# m328p_rfm69_node.net
KiCad netlist of a schematic drawn in EAGLE
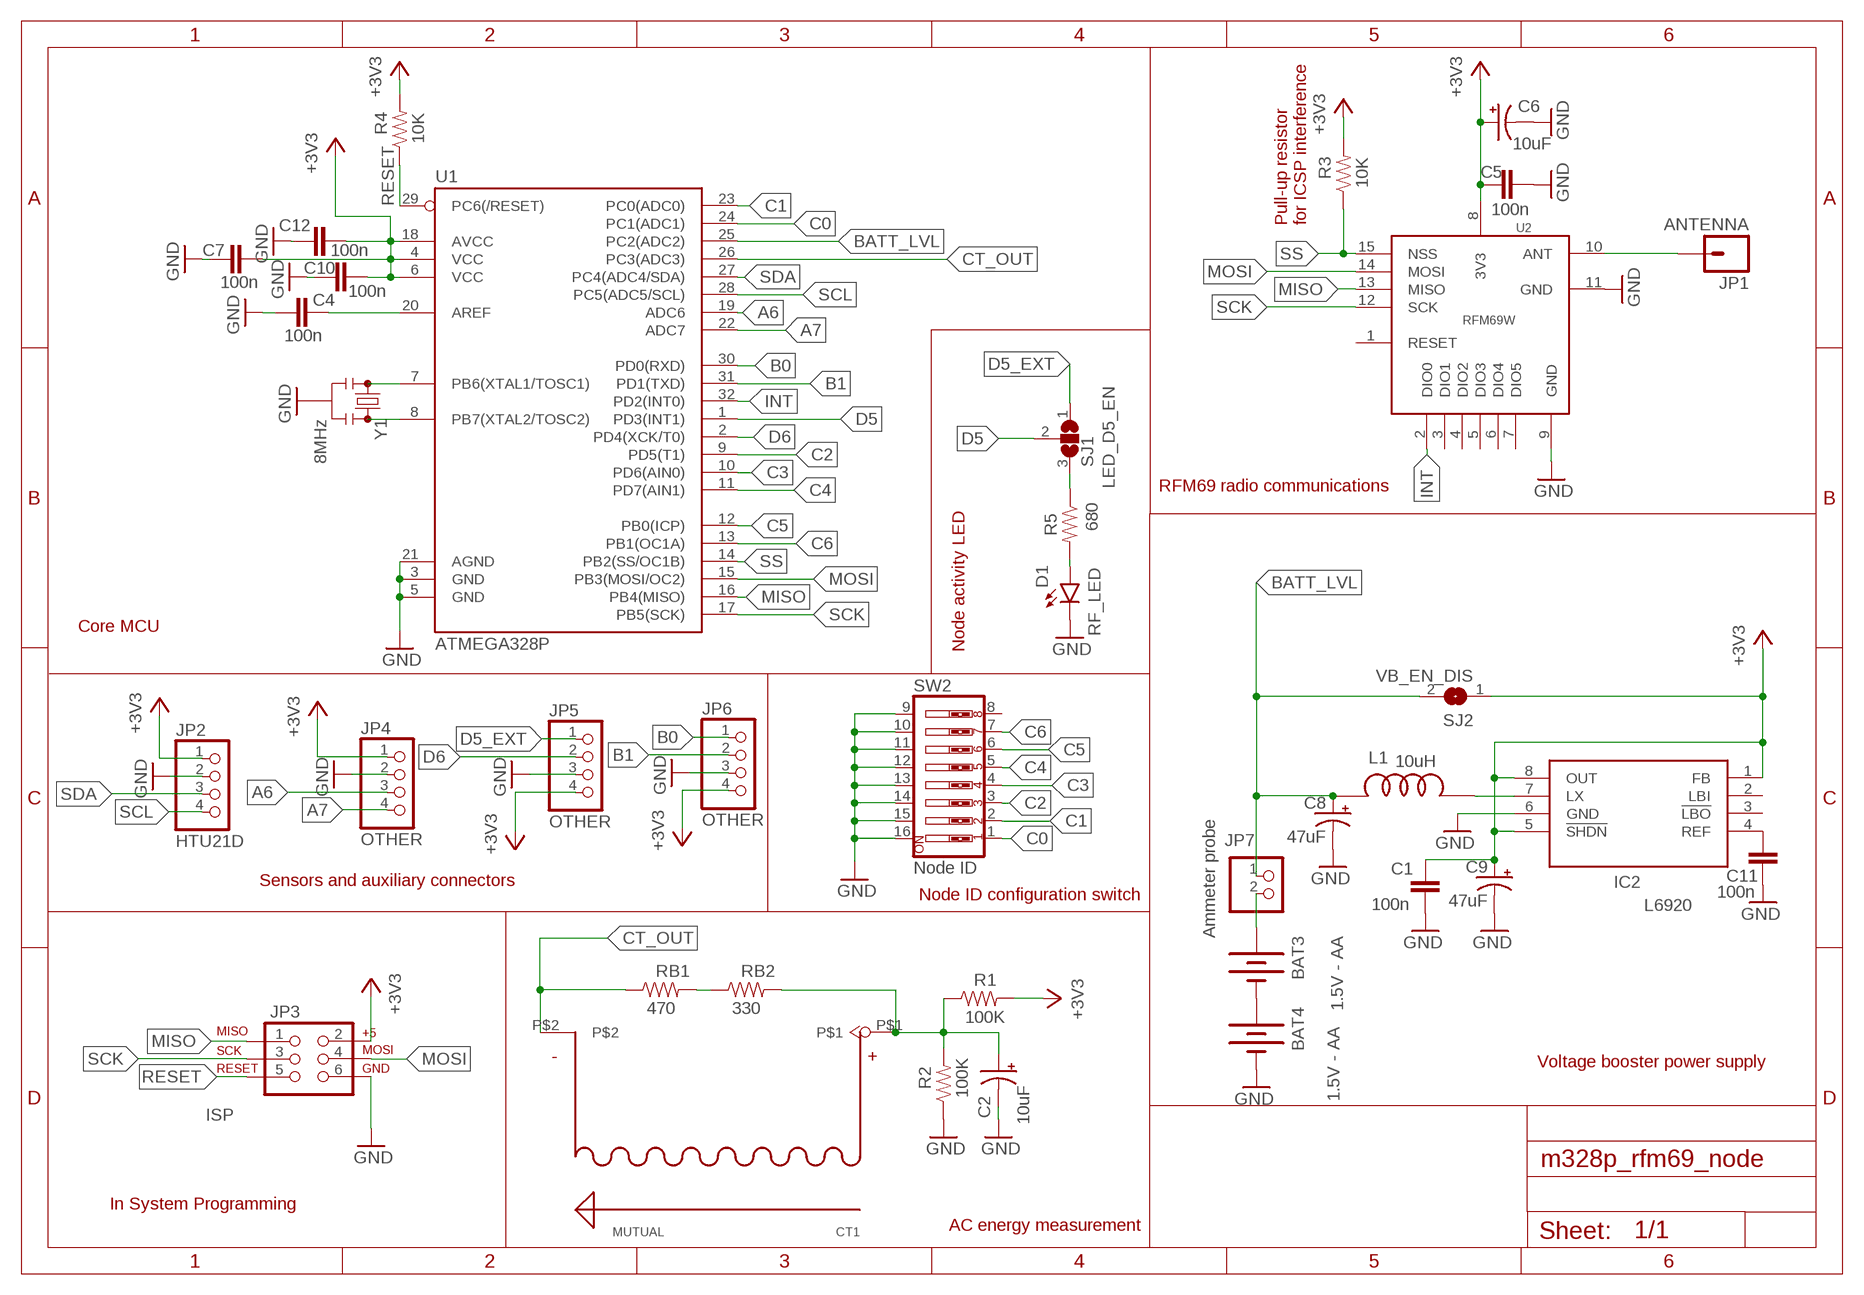
[diagram p0: schematic, sheet 1]

(export (version "E")
  (design (tool "Eeschema 10.0.6"))
  (components
    (comp (ref "BAT3")
      (value "1.5V - AA")
      (footprint "eagle-import:BATTERY-AAA-KIT")
      (libsource (lib "eagle-import") (part "BATTERYAAA-KIT"))
    )
    (comp (ref "BAT4")
      (value "1.5V - AA")
      (footprint "eagle-import:BATTERY-AAA-KIT")
      (libsource (lib "eagle-import") (part "BATTERYAAA-KIT"))
    )
    (comp (ref "C1")
      (value "100n")
      (footprint "eagle-import:0805")
      (libsource (lib "eagle-import") (part "CAP0805"))
    )
    (comp (ref "C2")
      (value "10uF")
      (footprint "eagle-import:EIA3528")
      (libsource (lib "eagle-import") (part "47UF-TANT"))
    )
    (comp (ref "C4")
      (value "100n")
      (footprint "eagle-import:0805")
      (libsource (lib "eagle-import") (part "CAP0805"))
    )
    (comp (ref "C5")
      (value "100n")
      (footprint "eagle-import:0805")
      (libsource (lib "eagle-import") (part "CAP0805"))
    )
    (comp (ref "C6")
      (value "10uF")
      (footprint "eagle-import:EIA3528")
      (libsource (lib "eagle-import") (part "47UF-TANT"))
    )
    (comp (ref "C7")
      (value "100n")
      (footprint "eagle-import:0805")
      (libsource (lib "eagle-import") (part "CAP0805"))
    )
    (comp (ref "C8")
      (value "47uF")
      (footprint "eagle-import:EIA3528")
      (libsource (lib "eagle-import") (part "47UF-TANT"))
    )
    (comp (ref "C9")
      (value "47uF")
      (footprint "eagle-import:EIA3528")
      (libsource (lib "eagle-import") (part "47UF-TANT"))
    )
    (comp (ref "C10")
      (value "100n")
      (footprint "eagle-import:0805")
      (libsource (lib "eagle-import") (part "CAP0805"))
    )
    (comp (ref "C11")
      (value "100n")
      (footprint "eagle-import:0805")
      (libsource (lib "eagle-import") (part "CAP0805"))
    )
    (comp (ref "C12")
      (value "100n")
      (footprint "eagle-import:0805")
      (libsource (lib "eagle-import") (part "CAP0805"))
    )
    (comp (ref "CT1")
      (value "MUTUAL")
      (footprint "eagle-import:MUTUAL")
      (libsource (lib "eagle-import") (part "MUTUAL"))
    )
    (comp (ref "D1")
      (value "RF_LED")
      (footprint "eagle-import:LED-0603")
      (libsource (lib "eagle-import") (part "LED0603"))
    )
    (comp (ref "IC2")
      (value "L6920")
      (footprint "eagle-import:TSSOP8")
      (libsource (lib "eagle-import") (part "L6920TSSOP8"))
    )
    (comp (ref "JP1")
      (value "ANTENNA")
      (footprint "eagle-import:LUXEON-PAD")
      (libsource (lib "eagle-import") (part "M01SMD"))
    )
    (comp (ref "JP2")
      (value "HTU21D")
      (footprint "eagle-import:1X04")
      (libsource (lib "eagle-import") (part "PINHD-1X4"))
    )
    (comp (ref "JP3")
      (value "ISP")
      (footprint "eagle-import:2X3")
      (libsource (lib "eagle-import") (part "AVR_SPI_PRG_6PTH"))
    )
    (comp (ref "JP4")
      (value "OTHER")
      (footprint "eagle-import:1X04")
      (libsource (lib "eagle-import") (part "PINHD-1X4"))
    )
    (comp (ref "JP5")
      (value "OTHER")
      (footprint "eagle-import:1X04")
      (libsource (lib "eagle-import") (part "PINHD-1X4"))
    )
    (comp (ref "JP6")
      (value "OTHER")
      (footprint "eagle-import:1X04")
      (libsource (lib "eagle-import") (part "PINHD-1X4"))
    )
    (comp (ref "JP7")
      (value "Ammeter probe")
      (footprint "eagle-import:1X02")
      (libsource (lib "eagle-import") (part "PINHD-1X2"))
    )
    (comp (ref "L1")
      (value "10uH")
      (footprint "eagle-import:DLJ-4018")
      (libsource (lib "eagle-import") (part "DLJ-4018"))
    )
    (comp (ref "R1")
      (value "100K")
      (footprint "eagle-import:0805")
      (libsource (lib "eagle-import") (part "SparkFun-Resistors_RESISTOR0805-RES"))
    )
    (comp (ref "R2")
      (value "100K")
      (footprint "eagle-import:0805")
      (libsource (lib "eagle-import") (part "SparkFun-Resistors_RESISTOR0805-RES"))
    )
    (comp (ref "R3")
      (value "10K")
      (footprint "eagle-import:0805")
      (libsource (lib "eagle-import") (part "SparkFun-Resistors_RESISTOR0805-RES"))
    )
    (comp (ref "R4")
      (value "10K")
      (footprint "eagle-import:0805")
      (libsource (lib "eagle-import") (part "SparkFun-Resistors_RESISTOR0805-RES"))
    )
    (comp (ref "R5")
      (value "680")
      (footprint "eagle-import:0805")
      (libsource (lib "eagle-import") (part "RESISTOR0805-RES"))
    )
    (comp (ref "RB1")
      (value "470")
      (footprint "eagle-import:0805")
      (libsource (lib "eagle-import") (part "SparkFun-Resistors_RESISTOR0805-RES"))
    )
    (comp (ref "RB2")
      (value "330")
      (footprint "eagle-import:0805")
      (libsource (lib "eagle-import") (part "SparkFun-Resistors_RESISTOR0805-RES"))
    )
    (comp (ref "SJ1")
      (value "LED_D5_EN")
      (footprint "eagle-import:SJ_2")
      (libsource (lib "eagle-import") (part "SJ2W"))
    )
    (comp (ref "SJ2")
      (value "VB_EN_DIS")
      (footprint "eagle-import:SJ")
      (libsource (lib "eagle-import") (part "SJ"))
    )
    (comp (ref "SW2")
      (value "Node ID")
      (footprint "eagle-import:DIPSWITCH-08-50MIL")
      (libsource (lib "eagle-import") (part "SW_DIP-8-SMT-HALFSIZE"))
    )
    (comp (ref "U1")
      (value "ATMEGA328P")
      (footprint "eagle-import:TQFP32-08")
      (libsource (lib "eagle-import") (part "ATMEGA328P_TQFP"))
    )
    (comp (ref "U2")
      (value "RFM69W")
      (footprint "eagle-import:RFM69W")
      (libsource (lib "eagle-import") (part "RFM69W"))
    )
    (comp (ref "Y1")
      (value "8MHz")
      (footprint "eagle-import:RESONATOR-SMD_MED")
      (libsource (lib "eagle-import") (part "RESONATOR4MHZ"))
    )
  )
  (nets
    (net (code "1") (name "+3V3") (class "Default")
      (node (ref "C1") (pin "1") (pinfunction "1_1") (pintype "passive"))
      (node (ref "C10") (pin "2") (pinfunction "2_2") (pintype "passive"))
      (node (ref "C12") (pin "2") (pinfunction "2_2") (pintype "passive"))
      (node (ref "C5") (pin "1") (pinfunction "1_1") (pintype "passive"))
      (node (ref "C6") (pin "A") (pinfunction "+_A") (pintype "passive"))
      (node (ref "C7") (pin "2") (pinfunction "2_2") (pintype "passive"))
      (node (ref "C9") (pin "A") (pinfunction "+_A") (pintype "passive"))
      (node (ref "IC2") (pin "1") (pinfunction "FB_1") (pintype "bidirectional"))
      (node (ref "IC2") (pin "5") (pinfunction "~{SHDN}_5") (pintype "bidirectional"))
      (node (ref "IC2") (pin "8") (pinfunction "OUT_8") (pintype "bidirectional"))
      (node (ref "JP2") (pin "1") (pinfunction "1_1") (pintype "passive"))
      (node (ref "JP3") (pin "2") (pinfunction "2_2") (pintype "passive"))
      (node (ref "JP4") (pin "1") (pinfunction "1_1") (pintype "passive"))
      (node (ref "JP5") (pin "4") (pinfunction "4_4") (pintype "passive"))
      (node (ref "JP6") (pin "4") (pinfunction "4_4") (pintype "passive"))
      (node (ref "R1") (pin "2") (pinfunction "2_2") (pintype "passive"))
      (node (ref "R3") (pin "2") (pinfunction "2_2") (pintype "passive"))
      (node (ref "R4") (pin "2") (pinfunction "2_2") (pintype "passive"))
      (node (ref "SJ2") (pin "1") (pinfunction "1_1") (pintype "passive"))
      (node (ref "U1") (pin "18") (pinfunction "AVCC_18") (pintype "bidirectional"))
      (node (ref "U1") (pin "4") (pinfunction "VCC_4") (pintype "bidirectional"))
      (node (ref "U1") (pin "6") (pinfunction "VCC_6") (pintype "bidirectional"))
      (node (ref "U2") (pin "8") (pinfunction "3V3_8") (pintype "bidirectional"))
    )
    (net (code "2") (name "A6") (class "Default")
      (node (ref "JP4") (pin "3") (pinfunction "3_3") (pintype "passive"))
      (node (ref "U1") (pin "19") (pinfunction "ADC6_19") (pintype "bidirectional"))
    )
    (net (code "3") (name "A7") (class "Default")
      (node (ref "JP4") (pin "4") (pinfunction "4_4") (pintype "passive"))
      (node (ref "U1") (pin "22") (pinfunction "ADC7_22") (pintype "bidirectional"))
    )
    (net (code "4") (name "B0") (class "Default")
      (node (ref "JP6") (pin "1") (pinfunction "1_1") (pintype "passive"))
      (node (ref "U1") (pin "30") (pinfunction "PD0(RXD)_30") (pintype "bidirectional"))
    )
    (net (code "5") (name "B1") (class "Default")
      (node (ref "JP6") (pin "2") (pinfunction "2_2") (pintype "passive"))
      (node (ref "U1") (pin "31") (pinfunction "PD1(TXD)_31") (pintype "bidirectional"))
    )
    (net (code "6") (name "BATT_LVL") (class "Default")
      (node (ref "C8") (pin "A") (pinfunction "+_A") (pintype "passive"))
      (node (ref "JP7") (pin "1") (pinfunction "1_1") (pintype "passive"))
      (node (ref "L1") (pin "P$2") (pinfunction "2_P$2") (pintype "bidirectional"))
      (node (ref "SJ2") (pin "2") (pinfunction "2_2") (pintype "passive"))
      (node (ref "U1") (pin "25") (pinfunction "PC2(ADC2)_25") (pintype "bidirectional"))
    )
    (net (code "7") (name "C0") (class "Default")
      (node (ref "SW2") (pin "1") (pinfunction "1_1") (pintype "passive"))
      (node (ref "U1") (pin "24") (pinfunction "PC1(ADC1)_24") (pintype "bidirectional"))
    )
    (net (code "8") (name "C1") (class "Default")
      (node (ref "SW2") (pin "2") (pinfunction "2_2") (pintype "passive"))
      (node (ref "U1") (pin "23") (pinfunction "PC0(ADC0)_23") (pintype "bidirectional"))
    )
    (net (code "9") (name "C2") (class "Default")
      (node (ref "SW2") (pin "3") (pinfunction "3_3") (pintype "passive"))
      (node (ref "U1") (pin "9") (pinfunction "PD5(T1)_9") (pintype "bidirectional"))
    )
    (net (code "10") (name "C3") (class "Default")
      (node (ref "SW2") (pin "4") (pinfunction "4_4") (pintype "passive"))
      (node (ref "U1") (pin "10") (pinfunction "PD6(AIN0)_10") (pintype "bidirectional"))
    )
    (net (code "11") (name "C4") (class "Default")
      (node (ref "SW2") (pin "5") (pinfunction "5_5") (pintype "passive"))
      (node (ref "U1") (pin "11") (pinfunction "PD7(AIN1)_11") (pintype "bidirectional"))
    )
    (net (code "12") (name "C5") (class "Default")
      (node (ref "SW2") (pin "6") (pinfunction "6_6") (pintype "passive"))
      (node (ref "U1") (pin "12") (pinfunction "PB0(ICP)_12") (pintype "bidirectional"))
    )
    (net (code "13") (name "C6") (class "Default")
      (node (ref "SW2") (pin "7") (pinfunction "7_7") (pintype "passive"))
      (node (ref "U1") (pin "13") (pinfunction "PB1(OC1A)_13") (pintype "bidirectional"))
    )
    (net (code "14") (name "CT_OUT") (class "Default")
      (node (ref "CT1") (pin "P$2") (pinfunction "P$2_P$2") (pintype "bidirectional"))
      (node (ref "RB1") (pin "1") (pinfunction "1_1") (pintype "passive"))
      (node (ref "U1") (pin "26") (pinfunction "PC3(ADC3)_26") (pintype "bidirectional"))
    )
    (net (code "15") (name "D5") (class "Default")
      (node (ref "SJ1") (pin "2") (pinfunction "2_2") (pintype "passive"))
      (node (ref "U1") (pin "1") (pinfunction "PD3(INT1)_1") (pintype "bidirectional"))
    )
    (net (code "16") (name "D5_EXT") (class "Default")
      (node (ref "JP5") (pin "1") (pinfunction "1_1") (pintype "passive"))
      (node (ref "SJ1") (pin "1") (pinfunction "1_1") (pintype "passive"))
    )
    (net (code "17") (name "D6") (class "Default")
      (node (ref "JP5") (pin "2") (pinfunction "2_2") (pintype "passive"))
      (node (ref "U1") (pin "2") (pinfunction "PD4(XCK/T0)_2") (pintype "bidirectional"))
    )
    (net (code "18") (name "GND") (class "Default")
      (node (ref "BAT4") (pin "GND@1") (pinfunction "-_GND@1") (pintype "power_in"))
      (node (ref "C1") (pin "2") (pinfunction "2_2") (pintype "passive"))
      (node (ref "C10") (pin "1") (pinfunction "1_1") (pintype "passive"))
      (node (ref "C11") (pin "2") (pinfunction "2_2") (pintype "passive"))
      (node (ref "C12") (pin "1") (pinfunction "1_1") (pintype "passive"))
      (node (ref "C2") (pin "C") (pinfunction "-_C") (pintype "passive"))
      (node (ref "C4") (pin "1") (pinfunction "1_1") (pintype "passive"))
      (node (ref "C5") (pin "2") (pinfunction "2_2") (pintype "passive"))
      (node (ref "C6") (pin "C") (pinfunction "-_C") (pintype "passive"))
      (node (ref "C7") (pin "1") (pinfunction "1_1") (pintype "passive"))
      (node (ref "C8") (pin "C") (pinfunction "-_C") (pintype "passive"))
      (node (ref "C9") (pin "C") (pinfunction "-_C") (pintype "passive"))
      (node (ref "D1") (pin "C") (pinfunction "C_C") (pintype "passive"))
      (node (ref "IC2") (pin "6") (pinfunction "GND_6") (pintype "bidirectional"))
      (node (ref "JP2") (pin "2") (pinfunction "2_2") (pintype "passive"))
      (node (ref "JP3") (pin "6") (pinfunction "6_6") (pintype "passive"))
      (node (ref "JP4") (pin "2") (pinfunction "2_2") (pintype "passive"))
      (node (ref "JP5") (pin "3") (pinfunction "3_3") (pintype "passive"))
      (node (ref "JP6") (pin "3") (pinfunction "3_3") (pintype "passive"))
      (node (ref "R2") (pin "1") (pinfunction "1_1") (pintype "passive"))
      (node (ref "SW2") (pin "10") (pinfunction "10_10") (pintype "passive"))
      (node (ref "SW2") (pin "11") (pinfunction "11_11") (pintype "passive"))
      (node (ref "SW2") (pin "12") (pinfunction "12_12") (pintype "passive"))
      (node (ref "SW2") (pin "13") (pinfunction "13_13") (pintype "passive"))
      (node (ref "SW2") (pin "14") (pinfunction "14_14") (pintype "passive"))
      (node (ref "SW2") (pin "15") (pinfunction "15_15") (pintype "passive"))
      (node (ref "SW2") (pin "16") (pinfunction "16_16") (pintype "passive"))
      (node (ref "SW2") (pin "9") (pinfunction "9_9") (pintype "passive"))
      (node (ref "U1") (pin "21") (pinfunction "AGND_21") (pintype "bidirectional"))
      (node (ref "U1") (pin "3") (pinfunction "GND_3") (pintype "bidirectional"))
      (node (ref "U1") (pin "5") (pinfunction "GND_5") (pintype "bidirectional"))
      (node (ref "U2") (pin "11") (pinfunction "GND_11") (pintype "bidirectional"))
      (node (ref "U2") (pin "9") (pinfunction "GND_9") (pintype "bidirectional"))
      (node (ref "Y1") (pin "2") (pinfunction "2_2") (pintype "passive"))
    )
    (net (code "19") (name "INT") (class "Default")
      (node (ref "U1") (pin "32") (pinfunction "PD2(INT0)_32") (pintype "bidirectional"))
      (node (ref "U2") (pin "2") (pinfunction "DIO0_2") (pintype "bidirectional"))
    )
    (net (code "20") (name "MISO") (class "Default")
      (node (ref "JP3") (pin "1") (pinfunction "1_1") (pintype "passive"))
      (node (ref "U1") (pin "16") (pinfunction "PB4(MISO)_16") (pintype "bidirectional"))
      (node (ref "U2") (pin "13") (pinfunction "MISO_13") (pintype "bidirectional"))
    )
    (net (code "21") (name "MOSI") (class "Default")
      (node (ref "JP3") (pin "4") (pinfunction "4_4") (pintype "passive"))
      (node (ref "U1") (pin "15") (pinfunction "PB3(MOSI/OC2)_15") (pintype "bidirectional"))
      (node (ref "U2") (pin "14") (pinfunction "MOSI_14") (pintype "bidirectional"))
    )
    (net (code "22") (name "Net-(BAT3-+)") (class "Default")
      (node (ref "BAT3") (pin "PWR@1") (pinfunction "+_PWR@1") (pintype "power_in"))
      (node (ref "JP7") (pin "2") (pinfunction "2_2") (pintype "passive"))
    )
    (net (code "23") (name "Net-(BAT3--)") (class "Default")
      (node (ref "BAT3") (pin "GND@1") (pinfunction "-_GND@1") (pintype "power_in"))
      (node (ref "BAT4") (pin "PWR@1") (pinfunction "+_PWR@1") (pintype "power_in"))
    )
    (net (code "24") (name "Net-(C2-+)") (class "Default")
      (node (ref "C2") (pin "A") (pinfunction "+_A") (pintype "passive"))
      (node (ref "CT1") (pin "P$1") (pinfunction "P$1_P$1") (pintype "bidirectional"))
      (node (ref "R1") (pin "1") (pinfunction "1_1") (pintype "passive"))
      (node (ref "R2") (pin "2") (pinfunction "2_2") (pintype "passive"))
      (node (ref "RB2") (pin "2") (pinfunction "2_2") (pintype "passive"))
    )
    (net (code "25") (name "Net-(D1-PadA)") (class "Default")
      (node (ref "D1") (pin "A") (pinfunction "A_A") (pintype "passive"))
      (node (ref "R5") (pin "2") (pinfunction "2_2") (pintype "passive"))
    )
    (net (code "26") (name "Net-(IC2-LX)") (class "Default")
      (node (ref "IC2") (pin "7") (pinfunction "LX_7") (pintype "bidirectional"))
      (node (ref "L1") (pin "P$1") (pinfunction "1_P$1") (pintype "bidirectional"))
    )
    (net (code "27") (name "Net-(IC2-REF)") (class "Default")
      (node (ref "C11") (pin "1") (pinfunction "1_1") (pintype "passive"))
      (node (ref "IC2") (pin "4") (pinfunction "REF_4") (pintype "bidirectional"))
    )
    (net (code "28") (name "Net-(JP1-1)") (class "Default")
      (node (ref "JP1") (pin "P$1") (pinfunction "1_P$1") (pintype "passive"))
      (node (ref "U2") (pin "10") (pinfunction "ANT_10") (pintype "bidirectional"))
    )
    (net (code "29") (name "Net-(R5-Pad1)") (class "Default")
      (node (ref "R5") (pin "1") (pinfunction "1_1") (pintype "passive"))
      (node (ref "SJ1") (pin "3") (pinfunction "3_3") (pintype "passive"))
    )
    (net (code "30") (name "Net-(RB1-Pad2)") (class "Default")
      (node (ref "RB1") (pin "2") (pinfunction "2_2") (pintype "passive"))
      (node (ref "RB2") (pin "1") (pinfunction "1_1") (pintype "passive"))
    )
    (net (code "31") (name "Net-(U1-AREF)") (class "Default")
      (node (ref "C4") (pin "2") (pinfunction "2_2") (pintype "passive"))
      (node (ref "U1") (pin "20") (pinfunction "AREF_20") (pintype "bidirectional"))
    )
    (net (code "32") (name "Net-(U1-PB6(XTAL1{slash}TOSC1))") (class "Default")
      (node (ref "U1") (pin "7") (pinfunction "PB6(XTAL1/TOSC1)_7") (pintype "bidirectional"))
      (node (ref "Y1") (pin "1") (pinfunction "1_1") (pintype "passive"))
    )
    (net (code "33") (name "Net-(U1-PB7(XTAL2{slash}TOSC2))") (class "Default")
      (node (ref "U1") (pin "8") (pinfunction "PB7(XTAL2/TOSC2)_8") (pintype "bidirectional"))
      (node (ref "Y1") (pin "3") (pinfunction "3_3") (pintype "passive"))
    )
    (net (code "34") (name "RESET") (class "Default")
      (node (ref "JP3") (pin "5") (pinfunction "5_5") (pintype "passive"))
      (node (ref "R4") (pin "1") (pinfunction "1_1") (pintype "passive"))
      (node (ref "U1") (pin "29") (pinfunction "PC6(/RESET)_29") (pintype "bidirectional"))
    )
    (net (code "35") (name "SCK") (class "Default")
      (node (ref "JP3") (pin "3") (pinfunction "3_3") (pintype "passive"))
      (node (ref "U1") (pin "17") (pinfunction "PB5(SCK)_17") (pintype "bidirectional"))
      (node (ref "U2") (pin "12") (pinfunction "SCK_12") (pintype "bidirectional"))
    )
    (net (code "36") (name "SCL") (class "Default")
      (node (ref "JP2") (pin "4") (pinfunction "4_4") (pintype "passive"))
      (node (ref "U1") (pin "28") (pinfunction "PC5(ADC5/SCL)_28") (pintype "bidirectional"))
    )
    (net (code "37") (name "SDA") (class "Default")
      (node (ref "JP2") (pin "3") (pinfunction "3_3") (pintype "passive"))
      (node (ref "U1") (pin "27") (pinfunction "PC4(ADC4/SDA)_27") (pintype "bidirectional"))
    )
    (net (code "38") (name "SS") (class "Default")
      (node (ref "R3") (pin "1") (pinfunction "1_1") (pintype "passive"))
      (node (ref "U1") (pin "14") (pinfunction "PB2(SS/OC1B)_14") (pintype "bidirectional"))
      (node (ref "U2") (pin "15") (pinfunction "NSS_15") (pintype "bidirectional"))
    )
    (net (code "39") (name "unconnected-(IC2-LBI-Pad2)") (class "Default")
      (node (ref "IC2") (pin "2") (pinfunction "LBI_2") (pintype "bidirectional"))
    )
    (net (code "40") (name "unconnected-(IC2-~{LBO}-Pad3)") (class "Default")
      (node (ref "IC2") (pin "3") (pinfunction "~{LBO}_3") (pintype "bidirectional"))
    )
    (net (code "41") (name "unconnected-(SW2-Pad8)") (class "Default")
      (node (ref "SW2") (pin "8") (pinfunction "8_8") (pintype "passive"))
    )
    (net (code "42") (name "unconnected-(U2-DIO1-Pad3)") (class "Default")
      (node (ref "U2") (pin "3") (pinfunction "DIO1_3") (pintype "bidirectional"))
    )
    (net (code "43") (name "unconnected-(U2-DIO2-Pad4)") (class "Default")
      (node (ref "U2") (pin "4") (pinfunction "DIO2_4") (pintype "bidirectional"))
    )
    (net (code "44") (name "unconnected-(U2-DIO3-Pad5)") (class "Default")
      (node (ref "U2") (pin "5") (pinfunction "DIO3_5") (pintype "bidirectional"))
    )
    (net (code "45") (name "unconnected-(U2-DIO4-Pad6)") (class "Default")
      (node (ref "U2") (pin "6") (pinfunction "DIO4_6") (pintype "bidirectional"))
    )
    (net (code "46") (name "unconnected-(U2-DIO5-Pad7)") (class "Default")
      (node (ref "U2") (pin "7") (pinfunction "DIO5_7") (pintype "bidirectional"))
    )
    (net (code "47") (name "unconnected-(U2-RESET-Pad1)") (class "Default")
      (node (ref "U2") (pin "1") (pinfunction "RESET_1") (pintype "bidirectional"))
    )
  )
)
